# Sheet1.net
KiCad netlist of a schematic drawn in Altium Designer
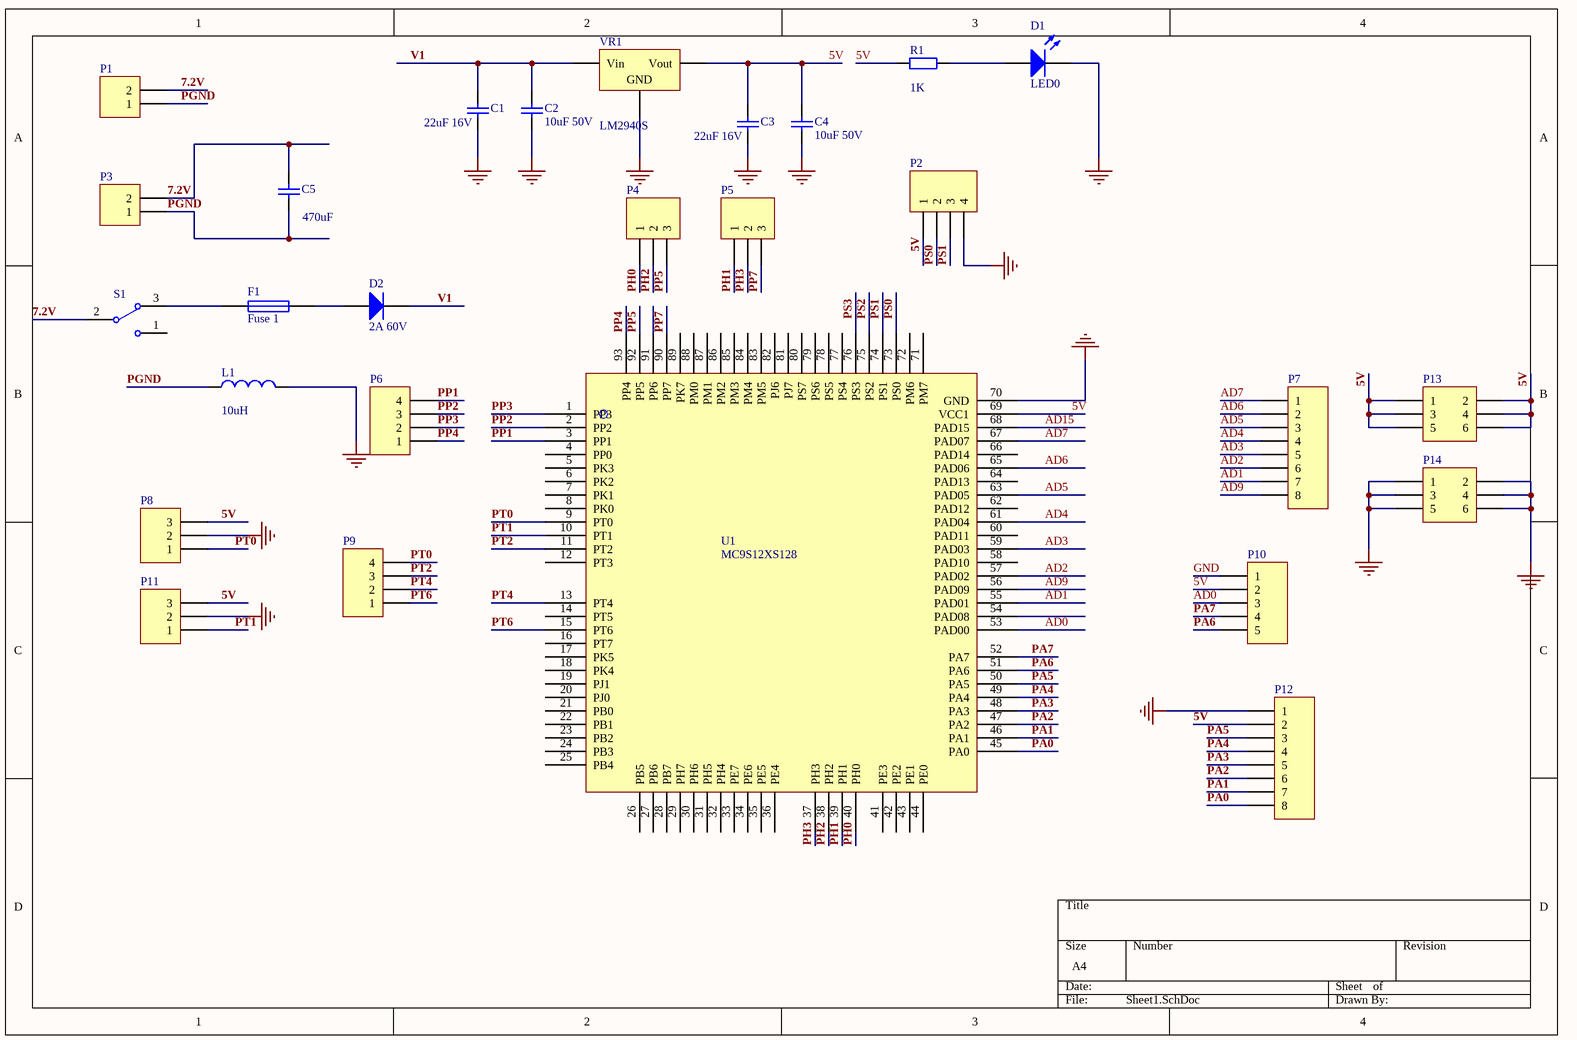
[diagram p0: Sheet1.SchDoc]

(export (version "E")
  (design (tool "Eeschema 10.0.6"))
  (components
    (comp (ref "C1")
      (value "22uF 16V")
      (footprint "22uF钽电容")
      (description "Capacitor")
      (fields (field (name "Comment") "Cap") (field (name "PUBLISHER") "Altium Limited"))
      (libsource (lib "Miscellaneous Devices") (part "Cap"))
    )
    (comp (ref "C2")
      (value "10uF 50V")
      (footprint "10uF的钽电容")
      (description "Capacitor")
      (fields (field (name "Comment") "Cap") (field (name "PUBLISHER") "Altium Limited"))
      (libsource (lib "Miscellaneous Devices") (part "Cap"))
    )
    (comp (ref "C3")
      (value "22uF 16V")
      (footprint "22uF钽电容")
      (description "Capacitor")
      (fields (field (name "Comment") "Cap") (field (name "PUBLISHER") "Altium Limited"))
      (libsource (lib "Miscellaneous Devices") (part "Cap"))
    )
    (comp (ref "C4")
      (value "10uF 50V")
      (footprint "10uF的钽电容")
      (description "Capacitor")
      (fields (field (name "Comment") "Cap") (field (name "PUBLISHER") "Altium Limited"))
      (libsource (lib "Miscellaneous Devices") (part "Cap"))
    )
    (comp (ref "C5")
      (value "470uF")
      (footprint "47UF钽电容")
      (description "Capacitor")
      (fields (field (name "Comment") "Cap") (field (name "PUBLISHER") "Altium Limited"))
      (libsource (lib "Miscellaneous Devices") (part "Cap"))
    )
    (comp (ref "D1")
      (value "LED0")
      (footprint "0805")
      (description "Typical INFRARED GaAs LED")
      (fields (field (name "PUBLISHER") "Altium Limited"))
      (libsource (lib "Miscellaneous Devices") (part "LED0"))
    )
    (comp (ref "D2")
      (value "2A 60V")
      (footprint "470uF钽电容")
      (description "1 Amp Fast Recovery Rectifier")
      (fields (field (name "PUBLISHER") "Altium Limited"))
      (libsource (lib "Miscellaneous Devices") (part "Diode 1N4934"))
    )
    (comp (ref "F1")
      (value "Fuse 1")
      (footprint "FUSE")
      (description "2A")
      (fields (field (name "PUBLISHER") "Altium Limited"))
      (libsource (lib "Miscellaneous Devices") (part "Fuse 1"))
    )
    (comp (ref "L1")
      (value "10uH")
      (footprint "MyPcbLib:INDUCTOR")
      (description "Inductor")
      (fields (field (name "PUBLISHER") "Altium Limited"))
      (libsource (lib "Miscellaneous Devices") (part "Inductor"))
    )
    (comp (ref "P1")
      (value "Header 2H")
      (footprint "端子")
      (description "Header, 2-Pin, Right Angle")
      (fields (field (name "PUBLISHER") "Altium Limited"))
      (libsource (lib "Miscellaneous Connectors") (part "Header 2H"))
    )
    (comp (ref "P2")
      (value "Header 4")
      (footprint "HDR1X4")
      (description "Header, 4-Pin")
      (fields (field (name "PUBLISHER") "Altium Limited"))
      (libsource (lib "") (part "Header 4_1"))
    )
    (comp (ref "P3")
      (value "Header 2")
      (footprint "端子")
      (description "Header, 2-Pin")
      (fields (field (name "PUBLISHER") "Altium Limited"))
      (libsource (lib "Miscellaneous Connectors") (part "Header 2"))
    )
    (comp (ref "P4")
      (value "Header 3")
      (footprint "HDR1X3")
      (description "Header, 3-Pin")
      (fields (field (name "PUBLISHER") "Altium Limited"))
      (libsource (lib "Miscellaneous Connectors") (part "Header 3"))
    )
    (comp (ref "P5")
      (value "Header 3")
      (footprint "HDR1X3")
      (description "Header, 3-Pin")
      (fields (field (name "PUBLISHER") "Altium Limited"))
      (libsource (lib "Miscellaneous Connectors") (part "Header 3"))
    )
    (comp (ref "P6")
      (value "Header 4")
      (footprint "HDR1X4")
      (description "Header, 4-Pin")
      (fields (field (name "PUBLISHER") "Altium Limited"))
      (libsource (lib "Miscellaneous Connectors") (part "Header 4"))
    )
    (comp (ref "P7")
      (value "Header 8")
      (footprint "HDR1X8")
      (description "Header, 8-Pin")
      (fields (field (name "PUBLISHER") "Altium Limited"))
      (libsource (lib "Miscellaneous Connectors") (part "Header 8"))
    )
    (comp (ref "P8")
      (value "Header 3")
      (footprint "HDR1X3")
      (description "Header, 3-Pin")
      (fields (field (name "PUBLISHER") "Altium Limited"))
      (libsource (lib "") (part "Header 3_1"))
    )
    (comp (ref "P9")
      (value "Header 4")
      (footprint "HDR1X4")
      (description "Header, 4-Pin")
      (fields (field (name "PUBLISHER") "Altium Limited"))
      (libsource (lib "Miscellaneous Connectors") (part "Header 4"))
    )
    (comp (ref "P10")
      (value "Header 5")
      (footprint "HDR1X5")
      (description "Header, 5-Pin")
      (fields (field (name "PUBLISHER") "Altium Limited"))
      (libsource (lib "Miscellaneous Connectors") (part "Header 5"))
    )
    (comp (ref "P11")
      (value "Header 3")
      (footprint "HDR1X3")
      (description "Header, 3-Pin")
      (fields (field (name "PUBLISHER") "Altium Limited"))
      (libsource (lib "") (part "Header 3_1"))
    )
    (comp (ref "P12")
      (value "Header 8")
      (footprint "HDR1X8")
      (description "Header, 8-Pin")
      (fields (field (name "PUBLISHER") "Altium Limited"))
      (libsource (lib "Miscellaneous Connectors") (part "Header 8"))
    )
    (comp (ref "P13")
      (value "Header 3X2")
      (footprint "HDR2X3")
      (description "Header, 3-Pin, Dual row")
      (fields (field (name "PUBLISHER") "Altium Limited"))
      (libsource (lib "Miscellaneous Connectors") (part "Header 3X2"))
    )
    (comp (ref "P14")
      (value "Header 3X2")
      (footprint "HDR2X3")
      (description "Header, 3-Pin, Dual row")
      (fields (field (name "PUBLISHER") "Altium Limited"))
      (libsource (lib "Miscellaneous Connectors") (part "Header 3X2"))
    )
    (comp (ref "R1")
      (value "1K")
      (footprint "0805")
      (description "Resistor")
      (fields (field (name "Comment") "Res2") (field (name "PUBLISHER") "Altium Limited"))
      (libsource (lib "Miscellaneous Devices") (part "Res2"))
    )
    (comp (ref "S1")
      (value "SW-SPDT")
      (footprint "Rockey_Switch")
      (description "SPDT Subminiature Toggle Switch, Right Angle Mounting, Vertical Actuation")
      (fields (field (name "PUBLISHER") "Altium Limited"))
      (libsource (lib "Miscellaneous Devices") (part "SW-SPDT"))
    )
    (comp (ref "U1") (value "MC9S12XS128") (footprint "XS128A") (libsource (lib "*") (part "MC9S12XS128")))
    (comp (ref "VR1")
      (value "LM2940S")
      (footprint "LM2940")
      (description "Voltage Regulator")
      (fields (field (name "PUBLISHER") "Altium Limited"))
      (libsource (lib "Miscellaneous Devices") (part "Volt Reg"))
    )
  )
  (nets
    (net (code "1") (name "/5V") (class "Default")
      (node (ref "C3") (pin "2") (pinfunction "2_2") (pintype "passive"))
      (node (ref "C4") (pin "2") (pinfunction "2_2") (pintype "passive"))
      (node (ref "P10") (pin "2") (pinfunction "2_2") (pintype "passive"))
      (node (ref "P11") (pin "3") (pinfunction "3_3") (pintype "passive"))
      (node (ref "P12") (pin "2") (pinfunction "2_2") (pintype "passive"))
      (node (ref "P13") (pin "1") (pinfunction "1_1") (pintype "passive"))
      (node (ref "P13") (pin "2") (pinfunction "2_2") (pintype "passive"))
      (node (ref "P13") (pin "3") (pinfunction "3_3") (pintype "passive"))
      (node (ref "P13") (pin "4") (pinfunction "4_4") (pintype "passive"))
      (node (ref "P13") (pin "5") (pinfunction "5_5") (pintype "passive"))
      (node (ref "P13") (pin "6") (pinfunction "6_6") (pintype "passive"))
      (node (ref "P2") (pin "1") (pinfunction "1_1") (pintype "passive"))
      (node (ref "P8") (pin "3") (pinfunction "3_3") (pintype "passive"))
      (node (ref "R1") (pin "1") (pinfunction "1_1") (pintype "passive"))
      (node (ref "U1") (pin "69") (pinfunction "VCC1_69") (pintype "passive"))
      (node (ref "VR1") (pin "3") (pinfunction "Vout_3") (pintype "passive"))
    )
    (net (code "2") (name "/7.2V") (class "Default")
      (node (ref "C5") (pin "2") (pinfunction "2_2") (pintype "passive"))
      (node (ref "P1") (pin "2") (pinfunction "2_2") (pintype "passive"))
      (node (ref "P3") (pin "2") (pinfunction "2_2") (pintype "passive"))
      (node (ref "S1") (pin "2") (pinfunction "2_2") (pintype "passive"))
    )
    (net (code "3") (name "/AD0") (class "Default")
      (node (ref "P10") (pin "3") (pinfunction "3_3") (pintype "passive"))
      (node (ref "U1") (pin "53") (pinfunction "PAD00_53") (pintype "passive"))
    )
    (net (code "4") (name "/AD1") (class "Default")
      (node (ref "P7") (pin "7") (pinfunction "7_7") (pintype "passive"))
      (node (ref "U1") (pin "55") (pinfunction "PAD01_55") (pintype "passive"))
    )
    (net (code "5") (name "/AD2") (class "Default")
      (node (ref "P7") (pin "6") (pinfunction "6_6") (pintype "passive"))
      (node (ref "U1") (pin "57") (pinfunction "PAD02_57") (pintype "passive"))
    )
    (net (code "6") (name "/AD3") (class "Default")
      (node (ref "P7") (pin "5") (pinfunction "5_5") (pintype "passive"))
      (node (ref "U1") (pin "59") (pinfunction "PAD03_59") (pintype "passive"))
    )
    (net (code "7") (name "/AD4") (class "Default")
      (node (ref "P7") (pin "4") (pinfunction "4_4") (pintype "passive"))
      (node (ref "U1") (pin "61") (pinfunction "PAD04_61") (pintype "passive"))
    )
    (net (code "8") (name "/AD5") (class "Default")
      (node (ref "P7") (pin "3") (pinfunction "3_3") (pintype "passive"))
      (node (ref "U1") (pin "63") (pinfunction "PAD05_63") (pintype "passive"))
    )
    (net (code "9") (name "/AD6") (class "Default")
      (node (ref "P7") (pin "2") (pinfunction "2_2") (pintype "passive"))
      (node (ref "U1") (pin "65") (pinfunction "PAD06_65") (pintype "passive"))
    )
    (net (code "10") (name "/AD7") (class "Default")
      (node (ref "P7") (pin "1") (pinfunction "1_1") (pintype "passive"))
      (node (ref "U1") (pin "67") (pinfunction "PAD07_67") (pintype "passive"))
    )
    (net (code "11") (name "/AD9") (class "Default")
      (node (ref "P7") (pin "8") (pinfunction "8_8") (pintype "passive"))
      (node (ref "U1") (pin "56") (pinfunction "PAD09_56") (pintype "passive"))
    )
    (net (code "12") (name "/AD15") (class "Default")
      (node (ref "U1") (pin "68") (pinfunction "PAD15_68") (pintype "passive"))
    )
    (net (code "13") (name "/PA0") (class "Default")
      (node (ref "P12") (pin "8") (pinfunction "8_8") (pintype "passive"))
      (node (ref "U1") (pin "45") (pinfunction "PA0_45") (pintype "passive"))
    )
    (net (code "14") (name "/PA1") (class "Default")
      (node (ref "P12") (pin "7") (pinfunction "7_7") (pintype "passive"))
      (node (ref "U1") (pin "46") (pinfunction "PA1_46") (pintype "passive"))
    )
    (net (code "15") (name "/PA2") (class "Default")
      (node (ref "P12") (pin "6") (pinfunction "6_6") (pintype "passive"))
      (node (ref "U1") (pin "47") (pinfunction "PA2_47") (pintype "passive"))
    )
    (net (code "16") (name "/PA3") (class "Default")
      (node (ref "P12") (pin "5") (pinfunction "5_5") (pintype "passive"))
      (node (ref "U1") (pin "48") (pinfunction "PA3_48") (pintype "passive"))
    )
    (net (code "17") (name "/PA4") (class "Default")
      (node (ref "P12") (pin "4") (pinfunction "4_4") (pintype "passive"))
      (node (ref "U1") (pin "49") (pinfunction "PA4_49") (pintype "passive"))
    )
    (net (code "18") (name "/PA5") (class "Default")
      (node (ref "P12") (pin "3") (pinfunction "3_3") (pintype "passive"))
      (node (ref "U1") (pin "50") (pinfunction "PA5_50") (pintype "passive"))
    )
    (net (code "19") (name "/PA6") (class "Default")
      (node (ref "P10") (pin "5") (pinfunction "5_5") (pintype "passive"))
      (node (ref "U1") (pin "51") (pinfunction "PA6_51") (pintype "passive"))
    )
    (net (code "20") (name "/PA7") (class "Default")
      (node (ref "P10") (pin "4") (pinfunction "4_4") (pintype "passive"))
      (node (ref "U1") (pin "52") (pinfunction "PA7_52") (pintype "passive"))
    )
    (net (code "21") (name "/PGND") (class "Default")
      (node (ref "C5") (pin "1") (pinfunction "1_1") (pintype "passive"))
      (node (ref "L1") (pin "1") (pinfunction "1_1") (pintype "passive"))
      (node (ref "P1") (pin "1") (pinfunction "1_1") (pintype "passive"))
      (node (ref "P3") (pin "1") (pinfunction "1_1") (pintype "passive"))
    )
    (net (code "22") (name "/PH0") (class "Default")
      (node (ref "P4") (pin "1") (pinfunction "1_1") (pintype "passive"))
      (node (ref "U1") (pin "40") (pinfunction "PH0_40") (pintype "passive"))
    )
    (net (code "23") (name "/PH1") (class "Default")
      (node (ref "P5") (pin "1") (pinfunction "1_1") (pintype "passive"))
      (node (ref "U1") (pin "39") (pinfunction "PH1_39") (pintype "passive"))
    )
    (net (code "24") (name "/PH2") (class "Default")
      (node (ref "P4") (pin "2") (pinfunction "2_2") (pintype "passive"))
      (node (ref "U1") (pin "38") (pinfunction "PH2_38") (pintype "passive"))
    )
    (net (code "25") (name "/PH3") (class "Default")
      (node (ref "P5") (pin "2") (pinfunction "2_2") (pintype "passive"))
      (node (ref "U1") (pin "37") (pinfunction "PH3_37") (pintype "passive"))
    )
    (net (code "26") (name "/PP1") (class "Default")
      (node (ref "P6") (pin "4") (pinfunction "4_4") (pintype "passive"))
      (node (ref "U1") (pin "3") (pinfunction "PP1_3") (pintype "passive"))
    )
    (net (code "27") (name "/PP2") (class "Default")
      (node (ref "P6") (pin "3") (pinfunction "3_3") (pintype "passive"))
      (node (ref "U1") (pin "2") (pinfunction "PP2_2") (pintype "passive"))
    )
    (net (code "28") (name "/PP3") (class "Default")
      (node (ref "P6") (pin "2") (pinfunction "2_2") (pintype "passive"))
      (node (ref "U1") (pin "1") (pinfunction "PP3_1") (pintype "passive"))
    )
    (net (code "29") (name "/PP4") (class "Default")
      (node (ref "P6") (pin "1") (pinfunction "1_1") (pintype "passive"))
      (node (ref "U1") (pin "93") (pinfunction "PP4_93") (pintype "passive"))
    )
    (net (code "30") (name "/PP5") (class "Default")
      (node (ref "P4") (pin "3") (pinfunction "3_3") (pintype "passive"))
      (node (ref "U1") (pin "92") (pinfunction "PP5_92") (pintype "passive"))
    )
    (net (code "31") (name "/PP7") (class "Default")
      (node (ref "P5") (pin "3") (pinfunction "3_3") (pintype "passive"))
      (node (ref "U1") (pin "90") (pinfunction "PP7_90") (pintype "passive"))
    )
    (net (code "32") (name "/PS0") (class "Default")
      (node (ref "P2") (pin "2") (pinfunction "2_2") (pintype "passive"))
      (node (ref "U1") (pin "73") (pinfunction "PS0_73") (pintype "passive"))
    )
    (net (code "33") (name "/PS1") (class "Default")
      (node (ref "P2") (pin "3") (pinfunction "3_3") (pintype "passive"))
      (node (ref "U1") (pin "74") (pinfunction "PS1_74") (pintype "passive"))
    )
    (net (code "34") (name "/PS2") (class "Default")
      (node (ref "U1") (pin "75") (pinfunction "PS2_75") (pintype "passive"))
    )
    (net (code "35") (name "/PS3") (class "Default")
      (node (ref "U1") (pin "76") (pinfunction "PS3_76") (pintype "passive"))
    )
    (net (code "36") (name "/PT0") (class "Default")
      (node (ref "P8") (pin "1") (pinfunction "1_1") (pintype "passive"))
      (node (ref "P9") (pin "4") (pinfunction "4_4") (pintype "passive"))
      (node (ref "U1") (pin "9") (pinfunction "PT0_9") (pintype "passive"))
    )
    (net (code "37") (name "/PT1") (class "Default")
      (node (ref "P11") (pin "1") (pinfunction "1_1") (pintype "passive"))
      (node (ref "U1") (pin "10") (pinfunction "PT1_10") (pintype "passive"))
    )
    (net (code "38") (name "/PT2") (class "Default")
      (node (ref "P9") (pin "3") (pinfunction "3_3") (pintype "passive"))
      (node (ref "U1") (pin "11") (pinfunction "PT2_11") (pintype "passive"))
    )
    (net (code "39") (name "/PT4") (class "Default")
      (node (ref "P9") (pin "2") (pinfunction "2_2") (pintype "passive"))
      (node (ref "U1") (pin "13") (pinfunction "PT4_13") (pintype "passive"))
    )
    (net (code "40") (name "/PT6") (class "Default")
      (node (ref "P9") (pin "1") (pinfunction "1_1") (pintype "passive"))
      (node (ref "U1") (pin "15") (pinfunction "PT6_15") (pintype "passive"))
    )
    (net (code "41") (name "/V1") (class "Default")
      (node (ref "C1") (pin "2") (pinfunction "2_2") (pintype "passive"))
      (node (ref "C2") (pin "2") (pinfunction "2_2") (pintype "passive"))
      (node (ref "D2") (pin "2") (pinfunction "K_2") (pintype "passive"))
      (node (ref "VR1") (pin "1") (pinfunction "Vin_1") (pintype "passive"))
    )
    (net (code "42") (name "GND") (class "Default")
      (node (ref "C1") (pin "1") (pinfunction "1_1") (pintype "passive"))
      (node (ref "C2") (pin "1") (pinfunction "1_1") (pintype "passive"))
      (node (ref "C3") (pin "1") (pinfunction "1_1") (pintype "passive"))
      (node (ref "C4") (pin "1") (pinfunction "1_1") (pintype "passive"))
      (node (ref "D1") (pin "2") (pinfunction "K_2") (pintype "passive"))
      (node (ref "L1") (pin "2") (pinfunction "2_2") (pintype "passive"))
      (node (ref "P10") (pin "1") (pinfunction "1_1") (pintype "passive"))
      (node (ref "P11") (pin "2") (pinfunction "2_2") (pintype "passive"))
      (node (ref "P12") (pin "1") (pinfunction "1_1") (pintype "passive"))
      (node (ref "P14") (pin "1") (pinfunction "1_1") (pintype "passive"))
      (node (ref "P14") (pin "2") (pinfunction "2_2") (pintype "passive"))
      (node (ref "P14") (pin "3") (pinfunction "3_3") (pintype "passive"))
      (node (ref "P14") (pin "4") (pinfunction "4_4") (pintype "passive"))
      (node (ref "P14") (pin "5") (pinfunction "5_5") (pintype "passive"))
      (node (ref "P14") (pin "6") (pinfunction "6_6") (pintype "passive"))
      (node (ref "P2") (pin "4") (pinfunction "4_4") (pintype "passive"))
      (node (ref "P8") (pin "2") (pinfunction "2_2") (pintype "passive"))
      (node (ref "U1") (pin "70") (pinfunction "GND_70") (pintype "passive"))
      (node (ref "VR1") (pin "2") (pinfunction "GND_2") (pintype "passive"))
    )
    (net (code "43") (name "Net-(D1-A)") (class "Default")
      (node (ref "D1") (pin "1") (pinfunction "A_1") (pintype "passive"))
      (node (ref "R1") (pin "2") (pinfunction "2_2") (pintype "passive"))
    )
    (net (code "44") (name "Net-(D2-A)") (class "Default")
      (node (ref "D2") (pin "1") (pinfunction "A_1") (pintype "passive"))
      (node (ref "F1") (pin "2") (pinfunction "2_2") (pintype "passive"))
    )
    (net (code "45") (name "Net-(F1-Pad1)") (class "Default")
      (node (ref "F1") (pin "1") (pinfunction "1_1") (pintype "passive"))
      (node (ref "S1") (pin "3") (pinfunction "3_3") (pintype "passive"))
    )
    (net (code "46") (name "unconnected-(S1-Pad1)") (class "Default")
      (node (ref "S1") (pin "1") (pinfunction "1_1") (pintype "passive"))
    )
    (net (code "47") (name "unconnected-(U1-PAD08-Pad54)") (class "Default")
      (node (ref "U1") (pin "54") (pinfunction "PAD08_54") (pintype "passive"))
    )
    (net (code "48") (name "unconnected-(U1-PAD10-Pad58)") (class "Default")
      (node (ref "U1") (pin "58") (pinfunction "PAD10_58") (pintype "passive"))
    )
    (net (code "49") (name "unconnected-(U1-PAD11-Pad60)") (class "Default")
      (node (ref "U1") (pin "60") (pinfunction "PAD11_60") (pintype "passive"))
    )
    (net (code "50") (name "unconnected-(U1-PAD12-Pad62)") (class "Default")
      (node (ref "U1") (pin "62") (pinfunction "PAD12_62") (pintype "passive"))
    )
    (net (code "51") (name "unconnected-(U1-PAD13-Pad64)") (class "Default")
      (node (ref "U1") (pin "64") (pinfunction "PAD13_64") (pintype "passive"))
    )
    (net (code "52") (name "unconnected-(U1-PAD14-Pad66)") (class "Default")
      (node (ref "U1") (pin "66") (pinfunction "PAD14_66") (pintype "passive"))
    )
    (net (code "53") (name "unconnected-(U1-PB0-Pad21)") (class "Default")
      (node (ref "U1") (pin "21") (pinfunction "PB0_21") (pintype "passive"))
    )
    (net (code "54") (name "unconnected-(U1-PB1-Pad22)") (class "Default")
      (node (ref "U1") (pin "22") (pinfunction "PB1_22") (pintype "passive"))
    )
    (net (code "55") (name "unconnected-(U1-PB2-Pad23)") (class "Default")
      (node (ref "U1") (pin "23") (pinfunction "PB2_23") (pintype "passive"))
    )
    (net (code "56") (name "unconnected-(U1-PB3-Pad24)") (class "Default")
      (node (ref "U1") (pin "24") (pinfunction "PB3_24") (pintype "passive"))
    )
    (net (code "57") (name "unconnected-(U1-PB4-Pad25)") (class "Default")
      (node (ref "U1") (pin "25") (pinfunction "PB4_25") (pintype "passive"))
    )
    (net (code "58") (name "unconnected-(U1-PB5-Pad26)") (class "Default")
      (node (ref "U1") (pin "26") (pinfunction "PB5_26") (pintype "passive"))
    )
    (net (code "59") (name "unconnected-(U1-PB6-Pad27)") (class "Default")
      (node (ref "U1") (pin "27") (pinfunction "PB6_27") (pintype "passive"))
    )
    (net (code "60") (name "unconnected-(U1-PB7-Pad28)") (class "Default")
      (node (ref "U1") (pin "28") (pinfunction "PB7_28") (pintype "passive"))
    )
    (net (code "61") (name "unconnected-(U1-PE0-Pad44)") (class "Default")
      (node (ref "U1") (pin "44") (pinfunction "PE0_44") (pintype "passive"))
    )
    (net (code "62") (name "unconnected-(U1-PE1-Pad43)") (class "Default")
      (node (ref "U1") (pin "43") (pinfunction "PE1_43") (pintype "passive"))
    )
    (net (code "63") (name "unconnected-(U1-PE2-Pad42)") (class "Default")
      (node (ref "U1") (pin "42") (pinfunction "PE2_42") (pintype "passive"))
    )
    (net (code "64") (name "unconnected-(U1-PE3-Pad41)") (class "Default")
      (node (ref "U1") (pin "41") (pinfunction "PE3_41") (pintype "passive"))
    )
    (net (code "65") (name "unconnected-(U1-PE4-Pad36)") (class "Default")
      (node (ref "U1") (pin "36") (pinfunction "PE4_36") (pintype "passive"))
    )
    (net (code "66") (name "unconnected-(U1-PE5-Pad35)") (class "Default")
      (node (ref "U1") (pin "35") (pinfunction "PE5_35") (pintype "passive"))
    )
    (net (code "67") (name "unconnected-(U1-PE6-Pad34)") (class "Default")
      (node (ref "U1") (pin "34") (pinfunction "PE6_34") (pintype "passive"))
    )
    (net (code "68") (name "unconnected-(U1-PE7-Pad33)") (class "Default")
      (node (ref "U1") (pin "33") (pinfunction "PE7_33") (pintype "passive"))
    )
    (net (code "69") (name "unconnected-(U1-PH4-Pad32)") (class "Default")
      (node (ref "U1") (pin "32") (pinfunction "PH4_32") (pintype "passive"))
    )
    (net (code "70") (name "unconnected-(U1-PH5-Pad31)") (class "Default")
      (node (ref "U1") (pin "31") (pinfunction "PH5_31") (pintype "passive"))
    )
    (net (code "71") (name "unconnected-(U1-PH6-Pad30)") (class "Default")
      (node (ref "U1") (pin "30") (pinfunction "PH6_30") (pintype "passive"))
    )
    (net (code "72") (name "unconnected-(U1-PH7-Pad29)") (class "Default")
      (node (ref "U1") (pin "29") (pinfunction "PH7_29") (pintype "passive"))
    )
    (net (code "73") (name "unconnected-(U1-PJ0-Pad20)") (class "Default")
      (node (ref "U1") (pin "20") (pinfunction "PJ0_20") (pintype "passive"))
    )
    (net (code "74") (name "unconnected-(U1-PJ1-Pad19)") (class "Default")
      (node (ref "U1") (pin "19") (pinfunction "PJ1_19") (pintype "passive"))
    )
    (net (code "75") (name "unconnected-(U1-PJ6-Pad82)") (class "Default")
      (node (ref "U1") (pin "82") (pinfunction "PJ6_82") (pintype "passive"))
    )
    (net (code "76") (name "unconnected-(U1-PJ7-Pad81)") (class "Default")
      (node (ref "U1") (pin "81") (pinfunction "PJ7_81") (pintype "passive"))
    )
    (net (code "77") (name "unconnected-(U1-PK0-Pad8)") (class "Default")
      (node (ref "U1") (pin "8") (pinfunction "PK0_8") (pintype "passive"))
    )
    (net (code "78") (name "unconnected-(U1-PK1-Pad7)") (class "Default")
      (node (ref "U1") (pin "7") (pinfunction "PK1_7") (pintype "passive"))
    )
    (net (code "79") (name "unconnected-(U1-PK2-Pad6)") (class "Default")
      (node (ref "U1") (pin "6") (pinfunction "PK2_6") (pintype "passive"))
    )
    (net (code "80") (name "unconnected-(U1-PK3-Pad5)") (class "Default")
      (node (ref "U1") (pin "5") (pinfunction "PK3_5") (pintype "passive"))
    )
    (net (code "81") (name "unconnected-(U1-PK4-Pad18)") (class "Default")
      (node (ref "U1") (pin "18") (pinfunction "PK4_18") (pintype "passive"))
    )
    (net (code "82") (name "unconnected-(U1-PK5-Pad17)") (class "Default")
      (node (ref "U1") (pin "17") (pinfunction "PK5_17") (pintype "passive"))
    )
    (net (code "83") (name "unconnected-(U1-PK7-Pad89)") (class "Default")
      (node (ref "U1") (pin "89") (pinfunction "PK7_89") (pintype "passive"))
    )
    (net (code "84") (name "unconnected-(U1-PM0-Pad88)") (class "Default")
      (node (ref "U1") (pin "88") (pinfunction "PM0_88") (pintype "passive"))
    )
    (net (code "85") (name "unconnected-(U1-PM1-Pad87)") (class "Default")
      (node (ref "U1") (pin "87") (pinfunction "PM1_87") (pintype "passive"))
    )
    (net (code "86") (name "unconnected-(U1-PM2-Pad86)") (class "Default")
      (node (ref "U1") (pin "86") (pinfunction "PM2_86") (pintype "passive"))
    )
    (net (code "87") (name "unconnected-(U1-PM3-Pad85)") (class "Default")
      (node (ref "U1") (pin "85") (pinfunction "PM3_85") (pintype "passive"))
    )
    (net (code "88") (name "unconnected-(U1-PM4-Pad84)") (class "Default")
      (node (ref "U1") (pin "84") (pinfunction "PM4_84") (pintype "passive"))
    )
    (net (code "89") (name "unconnected-(U1-PM5-Pad83)") (class "Default")
      (node (ref "U1") (pin "83") (pinfunction "PM5_83") (pintype "passive"))
    )
    (net (code "90") (name "unconnected-(U1-PM6-Pad72)") (class "Default")
      (node (ref "U1") (pin "72") (pinfunction "PM6_72") (pintype "passive"))
    )
    (net (code "91") (name "unconnected-(U1-PM7-Pad71)") (class "Default")
      (node (ref "U1") (pin "71") (pinfunction "PM7_71") (pintype "passive"))
    )
    (net (code "92") (name "unconnected-(U1-PP0-Pad4)") (class "Default")
      (node (ref "U1") (pin "4") (pinfunction "PP0_4") (pintype "passive"))
    )
    (net (code "93") (name "unconnected-(U1-PP6-Pad91)") (class "Default")
      (node (ref "U1") (pin "91") (pinfunction "PP6_91") (pintype "passive"))
    )
    (net (code "94") (name "unconnected-(U1-PS4-Pad77)") (class "Default")
      (node (ref "U1") (pin "77") (pinfunction "PS4_77") (pintype "passive"))
    )
    (net (code "95") (name "unconnected-(U1-PS5-Pad78)") (class "Default")
      (node (ref "U1") (pin "78") (pinfunction "PS5_78") (pintype "passive"))
    )
    (net (code "96") (name "unconnected-(U1-PS6-Pad79)") (class "Default")
      (node (ref "U1") (pin "79") (pinfunction "PS6_79") (pintype "passive"))
    )
    (net (code "97") (name "unconnected-(U1-PS7-Pad80)") (class "Default")
      (node (ref "U1") (pin "80") (pinfunction "PS7_80") (pintype "passive"))
    )
    (net (code "98") (name "unconnected-(U1-PT3-Pad12)") (class "Default")
      (node (ref "U1") (pin "12") (pinfunction "PT3_12") (pintype "passive"))
    )
    (net (code "99") (name "unconnected-(U1-PT5-Pad14)") (class "Default")
      (node (ref "U1") (pin "14") (pinfunction "PT5_14") (pintype "passive"))
    )
    (net (code "100") (name "unconnected-(U1-PT7-Pad16)") (class "Default")
      (node (ref "U1") (pin "16") (pinfunction "PT7_16") (pintype "passive"))
    )
  )
)
